# P1_Breakout.net
KiCad netlist of a schematic drawn in EAGLE
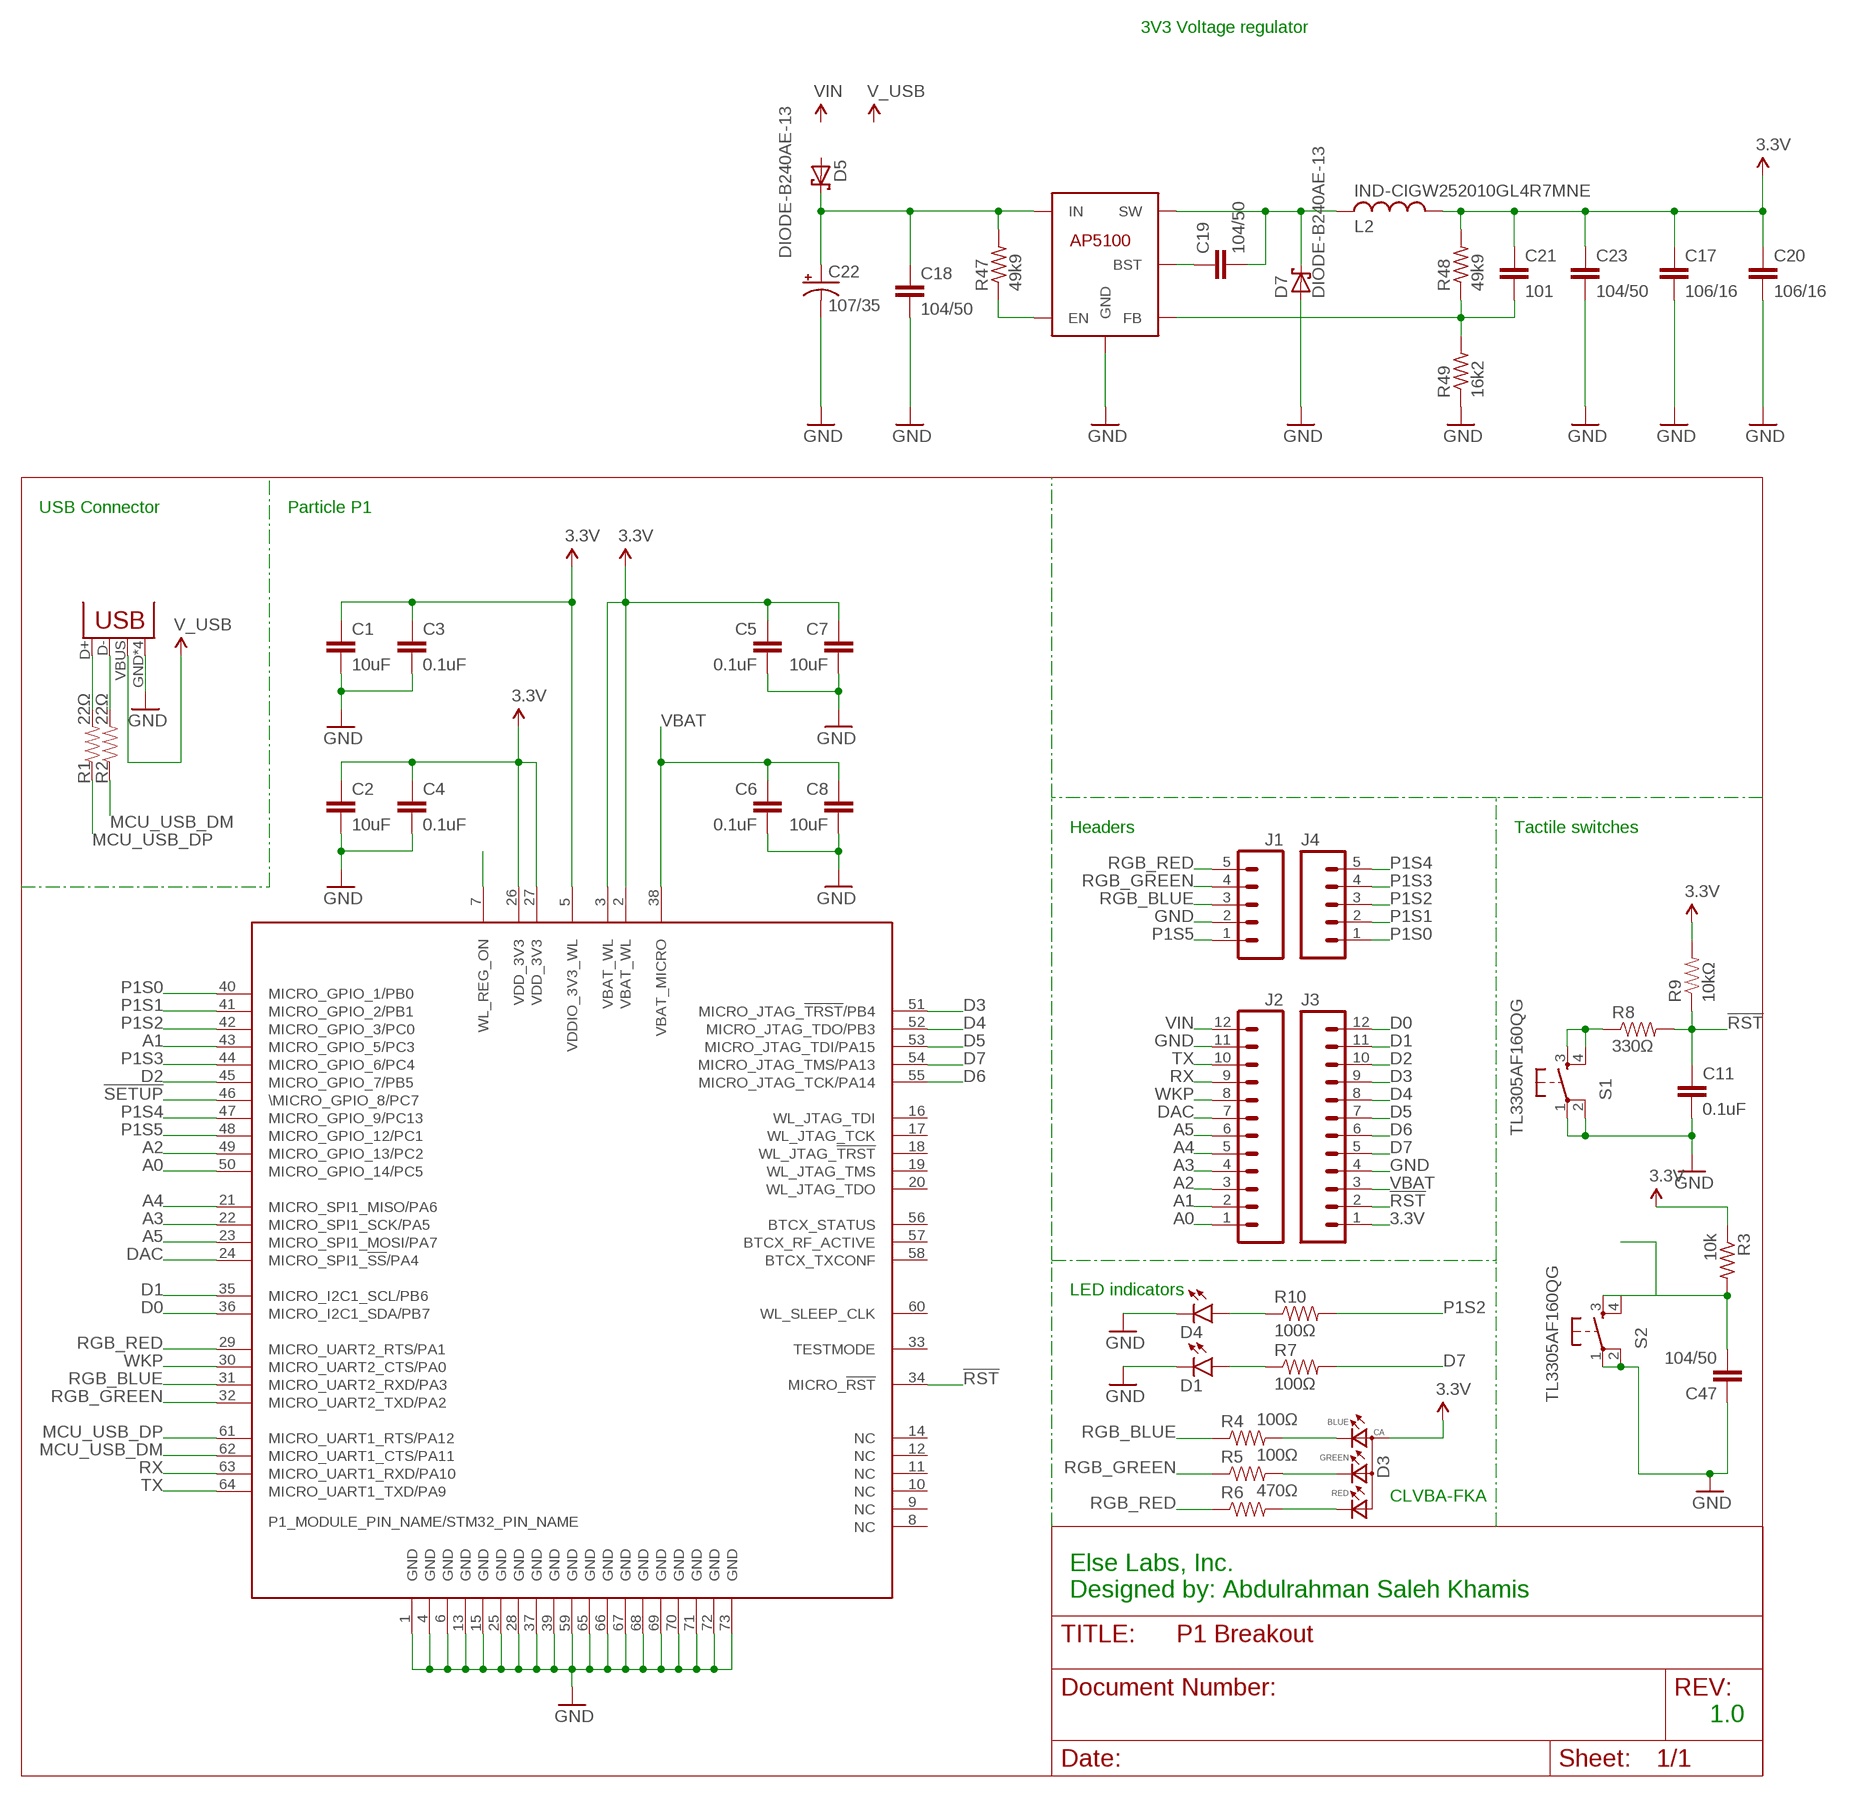
[diagram p0: schematic, sheet 1]

(export (version "E")
  (design (tool "Eeschema 10.0.6"))
  (components
    (comp (ref "C1")
      (value "10uF")
      (footprint "eagle-import:0805")
      (libsource (lib "eagle-import") (part "CAP0805"))
    )
    (comp (ref "C2")
      (value "10uF")
      (footprint "eagle-import:0805")
      (libsource (lib "eagle-import") (part "CAP0805"))
    )
    (comp (ref "C3")
      (value "0.1uF")
      (footprint "eagle-import:0805")
      (libsource (lib "eagle-import") (part "CAP0805"))
    )
    (comp (ref "C4")
      (value "0.1uF")
      (footprint "eagle-import:0805")
      (libsource (lib "eagle-import") (part "CAP0805"))
    )
    (comp (ref "C5")
      (value "0.1uF")
      (footprint "eagle-import:0805")
      (libsource (lib "eagle-import") (part "CAP0805"))
    )
    (comp (ref "C6")
      (value "0.1uF")
      (footprint "eagle-import:0805")
      (libsource (lib "eagle-import") (part "CAP0805"))
    )
    (comp (ref "C7")
      (value "10uF")
      (footprint "eagle-import:0805")
      (libsource (lib "eagle-import") (part "CAP0805"))
    )
    (comp (ref "C8")
      (value "10uF")
      (footprint "eagle-import:0805")
      (libsource (lib "eagle-import") (part "CAP0805"))
    )
    (comp (ref "C11")
      (value "0.1uF")
      (footprint "eagle-import:0805")
      (libsource (lib "eagle-import") (part "CAP0805"))
    )
    (comp (ref "C17")
      (value "106/16")
      (footprint "eagle-import:C0805")
      (libsource (lib "eagle-import") (part "C-EUC0805"))
    )
    (comp (ref "C18")
      (value "104/50")
      (footprint "eagle-import:C0603")
      (libsource (lib "eagle-import") (part "C-EUC0603"))
    )
    (comp (ref "C19")
      (value "104/50")
      (footprint "eagle-import:C0603")
      (libsource (lib "eagle-import") (part "C-EUC0603"))
    )
    (comp (ref "C20")
      (value "106/16")
      (footprint "eagle-import:C0805")
      (libsource (lib "eagle-import") (part "C-EUC0805"))
    )
    (comp (ref "C21")
      (value "101")
      (footprint "eagle-import:C0603")
      (libsource (lib "eagle-import") (part "C-EUC0603"))
    )
    (comp (ref "C22")
      (value "107/35")
      (footprint "eagle-import:UD-6,3X7,7_NICHICON")
      (libsource (lib "eagle-import") (part "CPOL-USUD-6,3X7,7"))
    )
    (comp (ref "C23")
      (value "104/50")
      (footprint "eagle-import:C0603")
      (libsource (lib "eagle-import") (part "C-EUC0603"))
    )
    (comp (ref "C47")
      (value "104/50")
      (footprint "eagle-import:C0603")
      (libsource (lib "eagle-import") (part "C-EUC0603"))
    )
    (comp (ref "D1")
      (value "LED0603")
      (footprint "eagle-import:LED-0603")
      (libsource (lib "eagle-import") (part "LED0603"))
    )
    (comp (ref "D3")
      (value "CLVBA-FKAPLCC")
      (footprint "eagle-import:4-PLCC")
      (libsource (lib "eagle-import") (part "CLVBA-FKAPLCC"))
    )
    (comp (ref "D4")
      (value "LED0603")
      (footprint "eagle-import:LED-0603")
      (libsource (lib "eagle-import") (part "LED0603"))
    )
    (comp (ref "D5")
      (value "DIODE-B240AE-13")
      (footprint "eagle-import:DO-214AC")
      (libsource (lib "eagle-import") (part "DIODE-B240AE-13"))
    )
    (comp (ref "D7")
      (value "DIODE-B240AE-13")
      (footprint "eagle-import:DO-214AC")
      (libsource (lib "eagle-import") (part "DIODE-B240AE-13"))
    )
    (comp (ref "IC5")
      (value "SMSP-BUCK-AP5100")
      (footprint "eagle-import:SOT23-6")
      (libsource (lib "eagle-import") (part "SMSP-BUCK-AP5100"))
    )
    (comp (ref "J1")
      (value "M05NO_SILK")
      (footprint "eagle-import:1X05_NO_SILK")
      (libsource (lib "eagle-import") (part "M05NO_SILK"))
    )
    (comp (ref "J2")
      (value "M12NO_SILK")
      (footprint "eagle-import:1X12_NO_SILK")
      (libsource (lib "eagle-import") (part "M12NO_SILK"))
    )
    (comp (ref "J3")
      (value "M12NO_SILK")
      (footprint "eagle-import:1X12_NO_SILK")
      (libsource (lib "eagle-import") (part "M12NO_SILK"))
    )
    (comp (ref "J4")
      (value "M05NO_SILK")
      (footprint "eagle-import:1X05_NO_SILK")
      (libsource (lib "eagle-import") (part "M05NO_SILK"))
    )
    (comp (ref "JP1")
      (value "USBUSB-MICROB-SLOT-HOLE")
      (footprint "eagle-import:USB-MICROB-SLOT-HOLE")
      (libsource (lib "eagle-import") (part "USBUSB-MICROB-SLOT-HOLE"))
    )
    (comp (ref "L2")
      (value "IND-CIGW252010GL4R7MNE")
      (footprint "eagle-import:L2520")
      (libsource (lib "eagle-import") (part "IND-CIGW252010GL4R7MNE"))
    )
    (comp (ref "R1")
      (value "22Ω")
      (footprint "eagle-import:0805")
      (libsource (lib "eagle-import") (part "RESISTOR0805-RES"))
    )
    (comp (ref "R2")
      (value "22Ω")
      (footprint "eagle-import:0805")
      (libsource (lib "eagle-import") (part "RESISTOR0805-RES"))
    )
    (comp (ref "R3")
      (value "10k")
      (footprint "eagle-import:R0603")
      (libsource (lib "eagle-import") (part "R-US_R0603"))
    )
    (comp (ref "R4")
      (value "100Ω")
      (footprint "eagle-import:0805")
      (libsource (lib "eagle-import") (part "RESISTOR0805-RES"))
    )
    (comp (ref "R5")
      (value "100Ω")
      (footprint "eagle-import:0805")
      (libsource (lib "eagle-import") (part "RESISTOR0805-RES"))
    )
    (comp (ref "R6")
      (value "470Ω")
      (footprint "eagle-import:0805")
      (libsource (lib "eagle-import") (part "RESISTOR0805-RES"))
    )
    (comp (ref "R7")
      (value "100Ω")
      (footprint "eagle-import:0805")
      (libsource (lib "eagle-import") (part "RESISTOR0805-RES"))
    )
    (comp (ref "R8")
      (value "330Ω")
      (footprint "eagle-import:0805")
      (libsource (lib "eagle-import") (part "RESISTOR0805-RES"))
    )
    (comp (ref "R9")
      (value "10kΩ")
      (footprint "eagle-import:0805")
      (libsource (lib "eagle-import") (part "RESISTOR0805-RES"))
    )
    (comp (ref "R10")
      (value "100Ω")
      (footprint "eagle-import:0805")
      (libsource (lib "eagle-import") (part "RESISTOR0805-RES"))
    )
    (comp (ref "R47")
      (value "49k9")
      (footprint "eagle-import:R0603")
      (libsource (lib "eagle-import") (part "R-US_R0603"))
    )
    (comp (ref "R48")
      (value "49k9")
      (footprint "eagle-import:R0603")
      (libsource (lib "eagle-import") (part "R-US_R0603"))
    )
    (comp (ref "R49")
      (value "16k2")
      (footprint "eagle-import:R0603")
      (libsource (lib "eagle-import") (part "R-US_R0603"))
    )
    (comp (ref "S1")
      (value "TL3305AF160QG")
      (footprint "eagle-import:TACTILE_SWITCH_SMD_4.5X4.5MM")
      (libsource (lib "eagle-import") (part "SWITCH-MOMENTARY-4.5MX4.5M"))
    )
    (comp (ref "S2")
      (value "TL3305AF160QG")
      (footprint "eagle-import:TACTILE_SWITCH_SMD_4.5X4.5MM")
      (libsource (lib "eagle-import") (part "SWITCH-MOMENTARY-4.5MX4.5M"))
    )
    (comp (ref "UC1")
      (value "P1")
      (footprint "eagle-import:WM-N-BM-14")
      (libsource (lib "eagle-import") (part "P1"))
    )
  )
  (nets
    (net (code "1") (name "/A0") (class "Default")
      (node (ref "J2") (pin "1") (pinfunction "1_1") (pintype "passive"))
      (node (ref "UC1") (pin "50") (pinfunction "MICRO_GPIO_14/PC5_50") (pintype "bidirectional"))
    )
    (net (code "2") (name "/A1") (class "Default")
      (node (ref "J2") (pin "2") (pinfunction "2_2") (pintype "passive"))
      (node (ref "UC1") (pin "43") (pinfunction "MICRO_GPIO_5/PC3_43") (pintype "bidirectional"))
    )
    (net (code "3") (name "/A2") (class "Default")
      (node (ref "J2") (pin "3") (pinfunction "3_3") (pintype "passive"))
      (node (ref "UC1") (pin "49") (pinfunction "MICRO_GPIO_13/PC2_49") (pintype "bidirectional"))
    )
    (net (code "4") (name "/A3") (class "Default")
      (node (ref "J2") (pin "4") (pinfunction "4_4") (pintype "passive"))
      (node (ref "UC1") (pin "22") (pinfunction "MICRO_SPI1_SCK/PA5_22") (pintype "bidirectional"))
    )
    (net (code "5") (name "/A4") (class "Default")
      (node (ref "J2") (pin "5") (pinfunction "5_5") (pintype "passive"))
      (node (ref "UC1") (pin "21") (pinfunction "MICRO_SPI1_MISO/PA6_21") (pintype "bidirectional"))
    )
    (net (code "6") (name "/A5") (class "Default")
      (node (ref "J2") (pin "6") (pinfunction "6_6") (pintype "passive"))
      (node (ref "UC1") (pin "23") (pinfunction "MICRO_SPI1_MOSI/PA7_23") (pintype "bidirectional"))
    )
    (net (code "7") (name "/D0") (class "Default")
      (node (ref "J3") (pin "12") (pinfunction "12_12") (pintype "passive"))
      (node (ref "UC1") (pin "36") (pinfunction "MICRO_I2C1_SDA/PB7_36") (pintype "bidirectional"))
    )
    (net (code "8") (name "/D1") (class "Default")
      (node (ref "J3") (pin "11") (pinfunction "11_11") (pintype "passive"))
      (node (ref "UC1") (pin "35") (pinfunction "MICRO_I2C1_SCL/PB6_35") (pintype "bidirectional"))
    )
    (net (code "9") (name "/D2") (class "Default")
      (node (ref "J3") (pin "10") (pinfunction "10_10") (pintype "passive"))
      (node (ref "UC1") (pin "45") (pinfunction "MICRO_GPIO_7/PB5_45") (pintype "bidirectional"))
    )
    (net (code "10") (name "/D3") (class "Default")
      (node (ref "J3") (pin "9") (pinfunction "9_9") (pintype "passive"))
      (node (ref "UC1") (pin "51") (pinfunction "MICRO_JTAG_~{TRST}/PB4_51") (pintype "bidirectional"))
    )
    (net (code "11") (name "/D4") (class "Default")
      (node (ref "J3") (pin "8") (pinfunction "8_8") (pintype "passive"))
      (node (ref "UC1") (pin "52") (pinfunction "MICRO_JTAG_TDO/PB3_52") (pintype "bidirectional"))
    )
    (net (code "12") (name "/D5") (class "Default")
      (node (ref "J3") (pin "7") (pinfunction "7_7") (pintype "passive"))
      (node (ref "UC1") (pin "53") (pinfunction "MICRO_JTAG_TDI/PA15_53") (pintype "bidirectional"))
    )
    (net (code "13") (name "/D6") (class "Default")
      (node (ref "J3") (pin "6") (pinfunction "6_6") (pintype "passive"))
      (node (ref "UC1") (pin "55") (pinfunction "MICRO_JTAG_TCK/PA14_55") (pintype "bidirectional"))
    )
    (net (code "14") (name "/D7") (class "Default")
      (node (ref "J3") (pin "5") (pinfunction "5_5") (pintype "passive"))
      (node (ref "R7") (pin "2") (pinfunction "2_2") (pintype "passive"))
      (node (ref "UC1") (pin "54") (pinfunction "MICRO_JTAG_TMS/PA13_54") (pintype "bidirectional"))
    )
    (net (code "15") (name "/DAC") (class "Default")
      (node (ref "J2") (pin "7") (pinfunction "7_7") (pintype "passive"))
      (node (ref "UC1") (pin "24") (pinfunction "MICRO_SPI1_~{SS}/PA4_24") (pintype "bidirectional"))
    )
    (net (code "16") (name "/MCU_USB_DM") (class "Default")
      (node (ref "R2") (pin "1") (pinfunction "1_1") (pintype "passive"))
      (node (ref "UC1") (pin "62") (pinfunction "MICRO_UART1_CTS/PA11_62") (pintype "bidirectional"))
    )
    (net (code "17") (name "/MCU_USB_DP") (class "Default")
      (node (ref "R1") (pin "1") (pinfunction "1_1") (pintype "passive"))
      (node (ref "UC1") (pin "61") (pinfunction "MICRO_UART1_RTS/PA12_61") (pintype "bidirectional"))
    )
    (net (code "18") (name "/P1S0") (class "Default")
      (node (ref "J4") (pin "1") (pinfunction "1_1") (pintype "passive"))
      (node (ref "UC1") (pin "40") (pinfunction "MICRO_GPIO_1/PB0_40") (pintype "bidirectional"))
    )
    (net (code "19") (name "/P1S1") (class "Default")
      (node (ref "J4") (pin "2") (pinfunction "2_2") (pintype "passive"))
      (node (ref "UC1") (pin "41") (pinfunction "MICRO_GPIO_2/PB1_41") (pintype "bidirectional"))
    )
    (net (code "20") (name "/P1S2") (class "Default")
      (node (ref "J4") (pin "3") (pinfunction "3_3") (pintype "passive"))
      (node (ref "R10") (pin "2") (pinfunction "2_2") (pintype "passive"))
      (node (ref "UC1") (pin "42") (pinfunction "MICRO_GPIO_3/PC0_42") (pintype "bidirectional"))
    )
    (net (code "21") (name "/P1S3") (class "Default")
      (node (ref "J4") (pin "4") (pinfunction "4_4") (pintype "passive"))
      (node (ref "UC1") (pin "44") (pinfunction "MICRO_GPIO_6/PC4_44") (pintype "bidirectional"))
    )
    (net (code "22") (name "/P1S4") (class "Default")
      (node (ref "J4") (pin "5") (pinfunction "5_5") (pintype "passive"))
      (node (ref "UC1") (pin "47") (pinfunction "MICRO_GPIO_9/PC13_47") (pintype "bidirectional"))
    )
    (net (code "23") (name "/P1S5") (class "Default")
      (node (ref "J1") (pin "1") (pinfunction "1_1") (pintype "passive"))
      (node (ref "UC1") (pin "48") (pinfunction "MICRO_GPIO_12/PC1_48") (pintype "bidirectional"))
    )
    (net (code "24") (name "/RGB_BLUE") (class "Default")
      (node (ref "J1") (pin "3") (pinfunction "3_3") (pintype "passive"))
      (node (ref "R4") (pin "1") (pinfunction "1_1") (pintype "passive"))
      (node (ref "UC1") (pin "31") (pinfunction "MICRO_UART2_RXD/PA3_31") (pintype "bidirectional"))
    )
    (net (code "25") (name "/RGB_GREEN") (class "Default")
      (node (ref "J1") (pin "4") (pinfunction "4_4") (pintype "passive"))
      (node (ref "R5") (pin "1") (pinfunction "1_1") (pintype "passive"))
      (node (ref "UC1") (pin "32") (pinfunction "MICRO_UART2_TXD/PA2_32") (pintype "bidirectional"))
    )
    (net (code "26") (name "/RGB_RED") (class "Default")
      (node (ref "J1") (pin "5") (pinfunction "5_5") (pintype "passive"))
      (node (ref "R6") (pin "1") (pinfunction "1_1") (pintype "passive"))
      (node (ref "UC1") (pin "29") (pinfunction "MICRO_UART2_RTS/PA1_29") (pintype "bidirectional"))
    )
    (net (code "27") (name "/RX") (class "Default")
      (node (ref "J2") (pin "9") (pinfunction "9_9") (pintype "passive"))
      (node (ref "UC1") (pin "63") (pinfunction "MICRO_UART1_RXD/PA10_63") (pintype "bidirectional"))
    )
    (net (code "28") (name "/TX") (class "Default")
      (node (ref "J2") (pin "10") (pinfunction "10_10") (pintype "passive"))
      (node (ref "UC1") (pin "64") (pinfunction "MICRO_UART1_TXD/PA9_64") (pintype "bidirectional"))
    )
    (net (code "29") (name "/VBAT") (class "Default")
      (node (ref "C6") (pin "1") (pinfunction "1_1") (pintype "passive"))
      (node (ref "C8") (pin "1") (pinfunction "1_1") (pintype "passive"))
      (node (ref "J3") (pin "3") (pinfunction "3_3") (pintype "passive"))
      (node (ref "UC1") (pin "38") (pinfunction "VBAT_MICRO_38") (pintype "bidirectional"))
    )
    (net (code "30") (name "/WKP") (class "Default")
      (node (ref "J2") (pin "8") (pinfunction "8_8") (pintype "passive"))
      (node (ref "UC1") (pin "30") (pinfunction "MICRO_UART2_CTS/PA0_30") (pintype "bidirectional"))
    )
    (net (code "31") (name "/~{RST}") (class "Default")
      (node (ref "C11") (pin "1") (pinfunction "1_1") (pintype "passive"))
      (node (ref "J3") (pin "2") (pinfunction "2_2") (pintype "passive"))
      (node (ref "R8") (pin "2") (pinfunction "2_2") (pintype "passive"))
      (node (ref "R9") (pin "1") (pinfunction "1_1") (pintype "passive"))
      (node (ref "UC1") (pin "34") (pinfunction "MICRO_~{RST}_34") (pintype "bidirectional"))
    )
    (net (code "32") (name "/~{SETUP}") (class "Default")
      (node (ref "UC1") (pin "46") (pinfunction "\\MICRO_GPIO_8/PC7_46") (pintype "bidirectional"))
    )
    (net (code "33") (name "3.3V") (class "Default")
      (node (ref "C1") (pin "1") (pinfunction "1_1") (pintype "passive"))
      (node (ref "C17") (pin "1") (pinfunction "1_1") (pintype "passive"))
      (node (ref "C2") (pin "1") (pinfunction "1_1") (pintype "passive"))
      (node (ref "C20") (pin "1") (pinfunction "1_1") (pintype "passive"))
      (node (ref "C21") (pin "1") (pinfunction "1_1") (pintype "passive"))
      (node (ref "C23") (pin "1") (pinfunction "1_1") (pintype "passive"))
      (node (ref "C3") (pin "1") (pinfunction "1_1") (pintype "passive"))
      (node (ref "C4") (pin "1") (pinfunction "1_1") (pintype "passive"))
      (node (ref "C5") (pin "1") (pinfunction "1_1") (pintype "passive"))
      (node (ref "C7") (pin "1") (pinfunction "1_1") (pintype "passive"))
      (node (ref "D3") (pin "2") (pinfunction "ANODE_2") (pintype "passive"))
      (node (ref "J3") (pin "1") (pinfunction "1_1") (pintype "passive"))
      (node (ref "L2") (pin "P$1") (pinfunction "1_P$1") (pintype "passive"))
      (node (ref "R3") (pin "1") (pinfunction "1_1") (pintype "passive"))
      (node (ref "R48") (pin "2") (pinfunction "2_2") (pintype "passive"))
      (node (ref "R9") (pin "2") (pinfunction "2_2") (pintype "passive"))
      (node (ref "UC1") (pin "2") (pinfunction "VBAT_WL_2") (pintype "bidirectional"))
      (node (ref "UC1") (pin "26") (pinfunction "VDD_3V3_26") (pintype "bidirectional"))
      (node (ref "UC1") (pin "27") (pinfunction "VDD_3V3_27") (pintype "bidirectional"))
      (node (ref "UC1") (pin "3") (pinfunction "VBAT_WL_3") (pintype "bidirectional"))
      (node (ref "UC1") (pin "5") (pinfunction "VDDIO_3V3_WL_5") (pintype "bidirectional"))
    )
    (net (code "34") (name "GND") (class "Default")
      (node (ref "C1") (pin "2") (pinfunction "2_2") (pintype "passive"))
      (node (ref "C11") (pin "2") (pinfunction "2_2") (pintype "passive"))
      (node (ref "C17") (pin "2") (pinfunction "2_2") (pintype "passive"))
      (node (ref "C18") (pin "2") (pinfunction "2_2") (pintype "passive"))
      (node (ref "C2") (pin "2") (pinfunction "2_2") (pintype "passive"))
      (node (ref "C20") (pin "2") (pinfunction "2_2") (pintype "passive"))
      (node (ref "C22") (pin "-") (pinfunction "-_-") (pintype "passive"))
      (node (ref "C23") (pin "2") (pinfunction "2_2") (pintype "passive"))
      (node (ref "C3") (pin "2") (pinfunction "2_2") (pintype "passive"))
      (node (ref "C4") (pin "2") (pinfunction "2_2") (pintype "passive"))
      (node (ref "C47") (pin "1") (pinfunction "1_1") (pintype "passive"))
      (node (ref "C5") (pin "2") (pinfunction "2_2") (pintype "passive"))
      (node (ref "C6") (pin "2") (pinfunction "2_2") (pintype "passive"))
      (node (ref "C7") (pin "2") (pinfunction "2_2") (pintype "passive"))
      (node (ref "C8") (pin "2") (pinfunction "2_2") (pintype "passive"))
      (node (ref "D1") (pin "C") (pinfunction "C_C") (pintype "passive"))
      (node (ref "D4") (pin "C") (pinfunction "C_C") (pintype "passive"))
      (node (ref "D7") (pin "A") (pinfunction "A_A") (pintype "passive"))
      (node (ref "IC5") (pin "2") (pinfunction "GND_2") (pintype "bidirectional"))
      (node (ref "J1") (pin "2") (pinfunction "2_2") (pintype "passive"))
      (node (ref "J2") (pin "11") (pinfunction "11_11") (pintype "passive"))
      (node (ref "J3") (pin "4") (pinfunction "4_4") (pintype "passive"))
      (node (ref "JP1") (pin "GND") (pinfunction "GND_GND") (pintype "bidirectional"))
      (node (ref "JP1") (pin "P$1") (pinfunction "GND_P$1") (pintype "bidirectional"))
      (node (ref "JP1") (pin "P$2") (pinfunction "GND_P$2") (pintype "bidirectional"))
      (node (ref "JP1") (pin "P$3") (pinfunction "GND_P$3") (pintype "bidirectional"))
      (node (ref "R49") (pin "1") (pinfunction "1_1") (pintype "passive"))
      (node (ref "S1") (pin "1") (pinfunction "1_1") (pintype "passive"))
      (node (ref "S1") (pin "2") (pinfunction "2_2") (pintype "passive"))
      (node (ref "S2") (pin "1") (pinfunction "1_1") (pintype "passive"))
      (node (ref "S2") (pin "2") (pinfunction "2_2") (pintype "passive"))
      (node (ref "UC1") (pin "1") (pinfunction "GND_1") (pintype "bidirectional"))
      (node (ref "UC1") (pin "13") (pinfunction "GND_13") (pintype "bidirectional"))
      (node (ref "UC1") (pin "15") (pinfunction "GND_15") (pintype "bidirectional"))
      (node (ref "UC1") (pin "25") (pinfunction "GND_25") (pintype "bidirectional"))
      (node (ref "UC1") (pin "28") (pinfunction "GND_28") (pintype "bidirectional"))
      (node (ref "UC1") (pin "37") (pinfunction "GND_37") (pintype "bidirectional"))
      (node (ref "UC1") (pin "39") (pinfunction "GND_39") (pintype "bidirectional"))
      (node (ref "UC1") (pin "4") (pinfunction "GND_4") (pintype "bidirectional"))
      (node (ref "UC1") (pin "59") (pinfunction "GND_59") (pintype "bidirectional"))
      (node (ref "UC1") (pin "6") (pinfunction "GND_6") (pintype "bidirectional"))
      (node (ref "UC1") (pin "65") (pinfunction "GND_65") (pintype "bidirectional"))
      (node (ref "UC1") (pin "66") (pinfunction "GND_66") (pintype "bidirectional"))
      (node (ref "UC1") (pin "67") (pinfunction "GND_67") (pintype "bidirectional"))
      (node (ref "UC1") (pin "68") (pinfunction "GND_68") (pintype "bidirectional"))
      (node (ref "UC1") (pin "69") (pinfunction "GND_69") (pintype "bidirectional"))
      (node (ref "UC1") (pin "70") (pinfunction "GND_70") (pintype "bidirectional"))
      (node (ref "UC1") (pin "71") (pinfunction "GND_71") (pintype "bidirectional"))
      (node (ref "UC1") (pin "72") (pinfunction "GND_72") (pintype "bidirectional"))
      (node (ref "UC1") (pin "73") (pinfunction "GND_73") (pintype "bidirectional"))
    )
    (net (code "35") (name "Net-(C47-Pad2)") (class "Default")
      (node (ref "C47") (pin "2") (pinfunction "2_2") (pintype "passive"))
      (node (ref "R3") (pin "2") (pinfunction "2_2") (pintype "passive"))
      (node (ref "S2") (pin "3") (pinfunction "3_3") (pintype "passive"))
    )
    (net (code "36") (name "Net-(D1-PadA)") (class "Default")
      (node (ref "D1") (pin "A") (pinfunction "A_A") (pintype "passive"))
      (node (ref "R7") (pin "1") (pinfunction "1_1") (pintype "passive"))
    )
    (net (code "37") (name "Net-(D3-BLUE)") (class "Default")
      (node (ref "D3") (pin "3") (pinfunction "BLUE_3") (pintype "passive"))
      (node (ref "R4") (pin "2") (pinfunction "2_2") (pintype "passive"))
    )
    (net (code "38") (name "Net-(D3-GREEN)") (class "Default")
      (node (ref "D3") (pin "4") (pinfunction "GREEN_4") (pintype "passive"))
      (node (ref "R5") (pin "2") (pinfunction "2_2") (pintype "passive"))
    )
    (net (code "39") (name "Net-(D3-RED)") (class "Default")
      (node (ref "D3") (pin "1") (pinfunction "RED_1") (pintype "passive"))
      (node (ref "R6") (pin "2") (pinfunction "2_2") (pintype "passive"))
    )
    (net (code "40") (name "Net-(D4-PadA)") (class "Default")
      (node (ref "D4") (pin "A") (pinfunction "A_A") (pintype "passive"))
      (node (ref "R10") (pin "1") (pinfunction "1_1") (pintype "passive"))
    )
    (net (code "41") (name "Net-(IC5-BST)") (class "Default")
      (node (ref "C19") (pin "1") (pinfunction "1_1") (pintype "passive"))
      (node (ref "IC5") (pin "1") (pinfunction "BST_1") (pintype "bidirectional"))
    )
    (net (code "42") (name "Net-(IC5-EN)") (class "Default")
      (node (ref "IC5") (pin "4") (pinfunction "EN_4") (pintype "bidirectional"))
      (node (ref "R47") (pin "1") (pinfunction "1_1") (pintype "passive"))
    )
    (net (code "43") (name "Net-(IC5-FB)") (class "Default")
      (node (ref "C21") (pin "2") (pinfunction "2_2") (pintype "passive"))
      (node (ref "IC5") (pin "3") (pinfunction "FB_3") (pintype "bidirectional"))
      (node (ref "R48") (pin "1") (pinfunction "1_1") (pintype "passive"))
      (node (ref "R49") (pin "2") (pinfunction "2_2") (pintype "passive"))
    )
    (net (code "44") (name "Net-(IC5-IN)") (class "Default")
      (node (ref "C18") (pin "1") (pinfunction "1_1") (pintype "passive"))
      (node (ref "C22") (pin "+") (pinfunction "+_+") (pintype "passive"))
      (node (ref "D5") (pin "C") (pinfunction "C_C") (pintype "passive"))
      (node (ref "IC5") (pin "5") (pinfunction "IN_5") (pintype "bidirectional"))
      (node (ref "R47") (pin "2") (pinfunction "2_2") (pintype "passive"))
    )
    (net (code "45") (name "Net-(IC5-SW)") (class "Default")
      (node (ref "C19") (pin "2") (pinfunction "2_2") (pintype "passive"))
      (node (ref "D7") (pin "C") (pinfunction "C_C") (pintype "passive"))
      (node (ref "IC5") (pin "6") (pinfunction "SW_6") (pintype "bidirectional"))
      (node (ref "L2") (pin "P$2") (pinfunction "2_P$2") (pintype "passive"))
    )
    (net (code "46") (name "Net-(JP1-PadD+)") (class "Default")
      (node (ref "JP1") (pin "D+") (pinfunction "D+_D+") (pintype "bidirectional"))
      (node (ref "R1") (pin "2") (pinfunction "2_2") (pintype "passive"))
    )
    (net (code "47") (name "Net-(JP1-PadD-)") (class "Default")
      (node (ref "JP1") (pin "D-") (pinfunction "D-_D-") (pintype "bidirectional"))
      (node (ref "R2") (pin "2") (pinfunction "2_2") (pintype "passive"))
    )
    (net (code "48") (name "Net-(R8-Pad1)") (class "Default")
      (node (ref "R8") (pin "1") (pinfunction "1_1") (pintype "passive"))
      (node (ref "S1") (pin "3") (pinfunction "3_3") (pintype "passive"))
      (node (ref "S1") (pin "4") (pinfunction "4_4") (pintype "passive"))
    )
    (net (code "49") (name "VIN") (class "Default")
      (node (ref "J2") (pin "12") (pinfunction "12_12") (pintype "passive"))
    )
    (net (code "50") (name "V_USB") (class "Default")
      (node (ref "JP1") (pin "VBUS") (pinfunction "VBUS_VBUS") (pintype "bidirectional"))
    )
    (net (code "51") (name "unconnected-(D5-PadA)") (class "Default")
      (node (ref "D5") (pin "A") (pinfunction "A_A") (pintype "passive"))
    )
    (net (code "52") (name "unconnected-(S2-Pad4)") (class "Default")
      (node (ref "S2") (pin "4") (pinfunction "4_4") (pintype "passive"))
    )
    (net (code "53") (name "unconnected-(UC1-BTCX_RF_ACTIVE-Pad57)") (class "Default")
      (node (ref "UC1") (pin "57") (pinfunction "BTCX_RF_ACTIVE_57") (pintype "bidirectional"))
    )
    (net (code "54") (name "unconnected-(UC1-BTCX_STATUS-Pad56)") (class "Default")
      (node (ref "UC1") (pin "56") (pinfunction "BTCX_STATUS_56") (pintype "bidirectional"))
    )
    (net (code "55") (name "unconnected-(UC1-BTCX_TXCONF-Pad58)") (class "Default")
      (node (ref "UC1") (pin "58") (pinfunction "BTCX_TXCONF_58") (pintype "bidirectional"))
    )
    (net (code "56") (name "unconnected-(UC1-NC-Pad8)") (class "Default")
      (node (ref "UC1") (pin "8") (pinfunction "NC_8") (pintype "bidirectional"))
    )
    (net (code "57") (name "unconnected-(UC1-NC-Pad9)") (class "Default")
      (node (ref "UC1") (pin "9") (pinfunction "NC_9") (pintype "bidirectional"))
    )
    (net (code "58") (name "unconnected-(UC1-NC-Pad10)") (class "Default")
      (node (ref "UC1") (pin "10") (pinfunction "NC_10") (pintype "bidirectional"))
    )
    (net (code "59") (name "unconnected-(UC1-NC-Pad11)") (class "Default")
      (node (ref "UC1") (pin "11") (pinfunction "NC_11") (pintype "bidirectional"))
    )
    (net (code "60") (name "unconnected-(UC1-NC-Pad12)") (class "Default")
      (node (ref "UC1") (pin "12") (pinfunction "NC_12") (pintype "bidirectional"))
    )
    (net (code "61") (name "unconnected-(UC1-NC-Pad14)") (class "Default")
      (node (ref "UC1") (pin "14") (pinfunction "NC_14") (pintype "bidirectional"))
    )
    (net (code "62") (name "unconnected-(UC1-TESTMODE-Pad33)") (class "Default")
      (node (ref "UC1") (pin "33") (pinfunction "TESTMODE_33") (pintype "bidirectional"))
    )
    (net (code "63") (name "unconnected-(UC1-WL_JTAG_TCK-Pad17)") (class "Default")
      (node (ref "UC1") (pin "17") (pinfunction "WL_JTAG_TCK_17") (pintype "bidirectional"))
    )
    (net (code "64") (name "unconnected-(UC1-WL_JTAG_TDI-Pad16)") (class "Default")
      (node (ref "UC1") (pin "16") (pinfunction "WL_JTAG_TDI_16") (pintype "bidirectional"))
    )
    (net (code "65") (name "unconnected-(UC1-WL_JTAG_TDO-Pad20)") (class "Default")
      (node (ref "UC1") (pin "20") (pinfunction "WL_JTAG_TDO_20") (pintype "bidirectional"))
    )
    (net (code "66") (name "unconnected-(UC1-WL_JTAG_TMS-Pad19)") (class "Default")
      (node (ref "UC1") (pin "19") (pinfunction "WL_JTAG_TMS_19") (pintype "bidirectional"))
    )
    (net (code "67") (name "unconnected-(UC1-WL_JTAG_~{TRST}-Pad18)") (class "Default")
      (node (ref "UC1") (pin "18") (pinfunction "WL_JTAG_~{TRST}_18") (pintype "bidirectional"))
    )
    (net (code "68") (name "unconnected-(UC1-WL_REG_ON-Pad7)") (class "Default")
      (node (ref "UC1") (pin "7") (pinfunction "WL_REG_ON_7") (pintype "bidirectional"))
    )
    (net (code "69") (name "unconnected-(UC1-WL_SLEEP_CLK-Pad60)") (class "Default")
      (node (ref "UC1") (pin "60") (pinfunction "WL_SLEEP_CLK_60") (pintype "bidirectional"))
    )
  )
)
